# linefollower_analog1.net
KiCad netlist of a schematic drawn in EAGLE
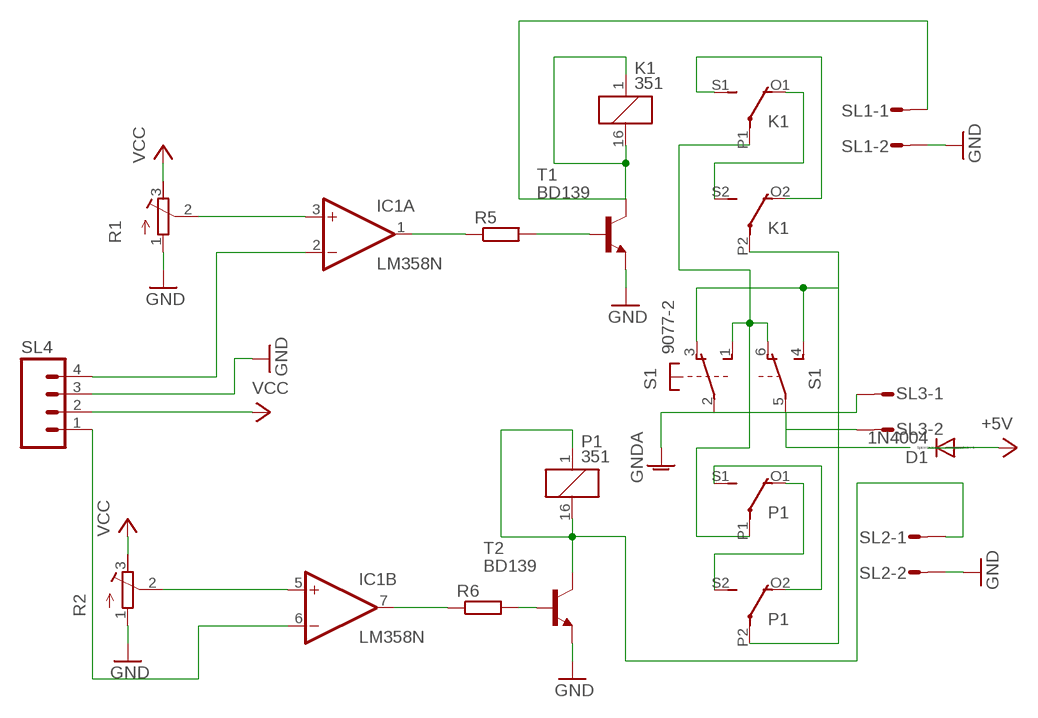
[diagram p0: schematic, sheet 1]

(export (version "E")
  (design (tool "Eeschema 10.0.6"))
  (components
    (comp (ref "D1")
      (value "1N4004")
      (footprint "eagle-import:DO41-10")
      (libsource (lib "eagle-import") (part "1N4004"))
    )
    (comp (ref "IC1")
      (value "LM358N")
      (footprint "eagle-import:DIL08")
      (libsource (lib "eagle-import") (part "LM358N"))
    )
    (comp (ref "K1")
      (value "351")
      (footprint "eagle-import:351")
      (libsource (lib "eagle-import") (part "351"))
    )
    (comp (ref "P1")
      (value "351")
      (footprint "eagle-import:351")
      (libsource (lib "eagle-import") (part "351"))
    )
    (comp (ref "R1")
      (value "R-TRIMM3339P")
      (footprint "eagle-import:RTRIM3339P")
      (libsource (lib "eagle-import") (part "R-TRIMM3339P"))
    )
    (comp (ref "R2")
      (value "R-TRIMM3339P")
      (footprint "eagle-import:RTRIM3339P")
      (libsource (lib "eagle-import") (part "R-TRIMM3339P"))
    )
    (comp (ref "R5")
      (value "R-EU_0207/7")
      (footprint "eagle-import:0207_7")
      (libsource (lib "eagle-import") (part "R-EU_0207/7"))
    )
    (comp (ref "R6")
      (value "R-EU_0207/7")
      (footprint "eagle-import:0207_7")
      (libsource (lib "eagle-import") (part "R-EU_0207/7"))
    )
    (comp (ref "S1")
      (value "9077-2")
      (footprint "eagle-import:9077-2")
      (libsource (lib "eagle-import") (part "9077-2"))
    )
    (comp (ref "SL1")
      (value "M02S")
      (footprint "eagle-import:02P")
      (libsource (lib "eagle-import") (part "M02S"))
    )
    (comp (ref "SL2")
      (value "M02S")
      (footprint "eagle-import:02P")
      (libsource (lib "eagle-import") (part "M02S"))
    )
    (comp (ref "SL3")
      (value "M02S")
      (footprint "eagle-import:02P")
      (libsource (lib "eagle-import") (part "M02S"))
    )
    (comp (ref "SL4")
      (value "M04")
      (footprint "eagle-import:04P")
      (libsource (lib "eagle-import") (part "M04"))
    )
    (comp (ref "T1")
      (value "BD139")
      (footprint "eagle-import:TO126")
      (libsource (lib "eagle-import") (part "BD139"))
    )
    (comp (ref "T2")
      (value "BD139")
      (footprint "eagle-import:TO126")
      (libsource (lib "eagle-import") (part "BD139"))
    )
  )
  (nets
    (net (code "1") (name "+5V") (class "Default")
      (node (ref "D1") (pin "A") (pinfunction "A_A") (pintype "passive"))
      (node (ref "D1") (pin "C") (pinfunction "C_C") (pintype "passive"))
    )
    (net (code "2") (name "GND") (class "Default")
      (node (ref "R1") (pin "1") (pinfunction "E_1") (pintype "passive"))
      (node (ref "R2") (pin "1") (pinfunction "E_1") (pintype "passive"))
      (node (ref "SL1") (pin "2") (pinfunction "S_2") (pintype "passive"))
      (node (ref "SL2") (pin "2") (pinfunction "S_2") (pintype "passive"))
      (node (ref "SL4") (pin "3") (pinfunction "3_3") (pintype "passive"))
      (node (ref "T1") (pin "1") (pinfunction "E_1") (pintype "passive"))
      (node (ref "T2") (pin "1") (pinfunction "E_1") (pintype "passive"))
    )
    (net (code "3") (name "GNDA") (class "Default")
      (node (ref "S1") (pin "2") (pinfunction "P_2") (pintype "passive"))
      (node (ref "SL3") (pin "1") (pinfunction "S_1") (pintype "passive"))
    )
    (net (code "4") (name "Net-(IC1A-+IN)") (class "Default")
      (node (ref "IC1") (pin "3") (pinfunction "+IN_3") (pintype "input"))
      (node (ref "R1") (pin "2") (pinfunction "S_2") (pintype "passive"))
    )
    (net (code "5") (name "Net-(IC1A--IN)") (class "Default")
      (node (ref "IC1") (pin "2") (pinfunction "-IN_2") (pintype "input"))
      (node (ref "SL4") (pin "4") (pinfunction "4_4") (pintype "passive"))
    )
    (net (code "6") (name "Net-(IC1A-OUT)") (class "Default")
      (node (ref "IC1") (pin "1") (pinfunction "OUT_1") (pintype "output"))
      (node (ref "R5") (pin "1") (pinfunction "1_1") (pintype "passive"))
    )
    (net (code "7") (name "Net-(IC1B-+IN)") (class "Default")
      (node (ref "IC1") (pin "5") (pinfunction "+IN_5") (pintype "input"))
      (node (ref "R2") (pin "2") (pinfunction "S_2") (pintype "passive"))
    )
    (net (code "8") (name "Net-(IC1B--IN)") (class "Default")
      (node (ref "IC1") (pin "6") (pinfunction "-IN_6") (pintype "input"))
      (node (ref "SL4") (pin "1") (pinfunction "1_1") (pintype "passive"))
    )
    (net (code "9") (name "Net-(IC1B-OUT)") (class "Default")
      (node (ref "IC1") (pin "7") (pinfunction "OUT_7") (pintype "output"))
      (node (ref "R6") (pin "1") (pinfunction "1_1") (pintype "passive"))
    )
    (net (code "10") (name "Net-(K1A-2)") (class "Default")
      (node (ref "K1") (pin "1") (pinfunction "1_1") (pintype "passive"))
      (node (ref "K1") (pin "16") (pinfunction "2_16") (pintype "passive"))
      (node (ref "SL1") (pin "1") (pinfunction "S_1") (pintype "passive"))
      (node (ref "T1") (pin "2") (pinfunction "C_2") (pintype "passive"))
    )
    (net (code "11") (name "Net-(K1B-O)") (class "Default")
      (node (ref "K1") (pin "O1") (pinfunction "O_O1") (pintype "passive"))
      (node (ref "K1") (pin "S2") (pinfunction "S_S2") (pintype "passive"))
    )
    (net (code "12") (name "Net-(K1B-P)") (class "Default")
      (node (ref "K1") (pin "P1") (pinfunction "P_P1") (pintype "passive"))
      (node (ref "P1") (pin "P1") (pinfunction "P_P1") (pintype "passive"))
      (node (ref "S1") (pin "1") (pinfunction "S_1") (pintype "passive"))
      (node (ref "S1") (pin "6") (pinfunction "O_6") (pintype "passive"))
    )
    (net (code "13") (name "Net-(K1B-S)") (class "Default")
      (node (ref "K1") (pin "O2") (pinfunction "O_O2") (pintype "passive"))
      (node (ref "K1") (pin "S1") (pinfunction "S_S1") (pintype "passive"))
    )
    (net (code "14") (name "Net-(K1C-P)") (class "Default")
      (node (ref "K1") (pin "P2") (pinfunction "P_P2") (pintype "passive"))
      (node (ref "P1") (pin "P2") (pinfunction "P_P2") (pintype "passive"))
      (node (ref "S1") (pin "3") (pinfunction "O_3") (pintype "passive"))
      (node (ref "S1") (pin "4") (pinfunction "S_4") (pintype "passive"))
    )
    (net (code "15") (name "Net-(P1A-2)") (class "Default")
      (node (ref "P1") (pin "1") (pinfunction "1_1") (pintype "passive"))
      (node (ref "P1") (pin "16") (pinfunction "2_16") (pintype "passive"))
      (node (ref "SL2") (pin "1") (pinfunction "S_1") (pintype "passive"))
      (node (ref "T2") (pin "2") (pinfunction "C_2") (pintype "passive"))
    )
    (net (code "16") (name "Net-(P1B-O)") (class "Default")
      (node (ref "P1") (pin "O1") (pinfunction "O_O1") (pintype "passive"))
      (node (ref "P1") (pin "S2") (pinfunction "S_S2") (pintype "passive"))
    )
    (net (code "17") (name "Net-(P1B-S)") (class "Default")
      (node (ref "P1") (pin "O2") (pinfunction "O_O2") (pintype "passive"))
      (node (ref "P1") (pin "S1") (pinfunction "S_S1") (pintype "passive"))
    )
    (net (code "18") (name "Net-(S1B-P)") (class "Default")
      (node (ref "S1") (pin "5") (pinfunction "P_5") (pintype "passive"))
      (node (ref "SL3") (pin "2") (pinfunction "S_2") (pintype "passive"))
    )
    (net (code "19") (name "Net-(T1-B)") (class "Default")
      (node (ref "R5") (pin "2") (pinfunction "2_2") (pintype "passive"))
      (node (ref "T1") (pin "3") (pinfunction "B_3") (pintype "passive"))
    )
    (net (code "20") (name "Net-(T2-B)") (class "Default")
      (node (ref "R6") (pin "2") (pinfunction "2_2") (pintype "passive"))
      (node (ref "T2") (pin "3") (pinfunction "B_3") (pintype "passive"))
    )
    (net (code "21") (name "VCC") (class "Default")
      (node (ref "R1") (pin "3") (pinfunction "A_3") (pintype "passive"))
      (node (ref "R2") (pin "3") (pinfunction "A_3") (pintype "passive"))
      (node (ref "SL4") (pin "2") (pinfunction "2_2") (pintype "passive"))
    )
  )
)
